# USBPiano.net
KiCad netlist of a schematic drawn in EAGLE
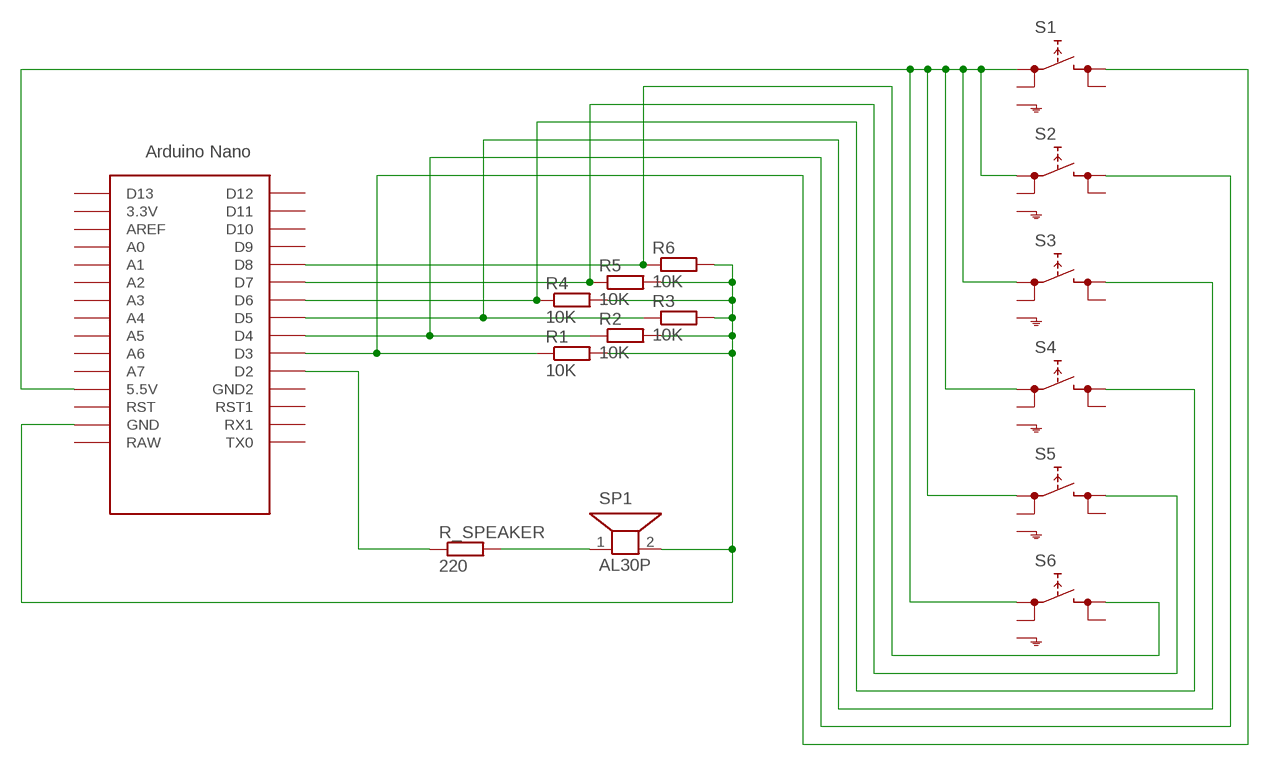
[diagram p0: schematic, sheet 1]

(export (version "E")
  (design (tool "Eeschema 10.0.6"))
  (components
    (comp (ref "R1")
      (value "10K")
      (footprint "eagle-import:M0805")
      (libsource (lib "eagle-import") (part "R-EU_M0805"))
    )
    (comp (ref "R2")
      (value "10K")
      (footprint "eagle-import:M0805")
      (libsource (lib "eagle-import") (part "R-EU_M0805"))
    )
    (comp (ref "R3")
      (value "10K")
      (footprint "eagle-import:M0805")
      (libsource (lib "eagle-import") (part "R-EU_M0805"))
    )
    (comp (ref "R4")
      (value "10K")
      (footprint "eagle-import:M0805")
      (libsource (lib "eagle-import") (part "R-EU_M0805"))
    )
    (comp (ref "R5")
      (value "10K")
      (footprint "eagle-import:M0805")
      (libsource (lib "eagle-import") (part "R-EU_M0805"))
    )
    (comp (ref "R6")
      (value "10K")
      (footprint "eagle-import:M0805")
      (libsource (lib "eagle-import") (part "R-EU_M0805"))
    )
    (comp (ref "R_SPEAKER")
      (value "220")
      (footprint "eagle-import:M0805")
      (libsource (lib "eagle-import") (part "R-EU_M0805"))
    )
    (comp (ref "S1")
      (value "SKHMPSE010")
      (footprint "eagle-import:SKHMPXE010")
      (libsource (lib "eagle-import") (part "SKHMPE010S"))
    )
    (comp (ref "S2")
      (value "SKHMPSE010")
      (footprint "eagle-import:SKHMPXE010")
      (libsource (lib "eagle-import") (part "SKHMPE010S"))
    )
    (comp (ref "S3")
      (value "SKHMPSE010")
      (footprint "eagle-import:SKHMPXE010")
      (libsource (lib "eagle-import") (part "SKHMPE010S"))
    )
    (comp (ref "S4")
      (value "SKHMPSE010")
      (footprint "eagle-import:SKHMPXE010")
      (libsource (lib "eagle-import") (part "SKHMPE010S"))
    )
    (comp (ref "S5")
      (value "SKHMPSE010")
      (footprint "eagle-import:SKHMPXE010")
      (libsource (lib "eagle-import") (part "SKHMPE010S"))
    )
    (comp (ref "S6")
      (value "SKHMPSE010")
      (footprint "eagle-import:SKHMPXE010")
      (libsource (lib "eagle-import") (part "SKHMPE010S"))
    )
    (comp (ref "SP1")
      (value "AL30P")
      (footprint "eagle-import:AL30P")
      (libsource (lib "eagle-import") (part "AL30P"))
    )
    (comp (ref "U$1")
      (value "NANO")
      (footprint "eagle-import:NANO")
      (libsource (lib "eagle-import") (part "NANO"))
    )
  )
  (nets
    (net (code "1") (name "Net-(R1-Pad2)") (class "Default")
      (node (ref "R1") (pin "2") (pinfunction "2_2") (pintype "passive"))
      (node (ref "R2") (pin "2") (pinfunction "2_2") (pintype "passive"))
      (node (ref "R3") (pin "2") (pinfunction "2_2") (pintype "passive"))
      (node (ref "R4") (pin "2") (pinfunction "2_2") (pintype "passive"))
      (node (ref "R5") (pin "2") (pinfunction "2_2") (pintype "passive"))
      (node (ref "R6") (pin "2") (pinfunction "2_2") (pintype "passive"))
      (node (ref "SP1") (pin "2") (pinfunction "2_2") (pintype "passive"))
      (node (ref "U$1") (pin "GND") (pinfunction "GND_GND") (pintype "bidirectional"))
    )
    (net (code "2") (name "Net-(R_SPEAKER-Pad1)") (class "Default")
      (node (ref "R_SPEAKER") (pin "1") (pinfunction "1_1") (pintype "passive"))
      (node (ref "U$1") (pin "D2") (pinfunction "D2_D2") (pintype "bidirectional"))
    )
    (net (code "3") (name "Net-(R_SPEAKER-Pad2)") (class "Default")
      (node (ref "R_SPEAKER") (pin "2") (pinfunction "2_2") (pintype "passive"))
      (node (ref "SP1") (pin "1") (pinfunction "1_1") (pintype "passive"))
    )
    (net (code "4") (name "Net-(S1-1.1)") (class "Default")
      (node (ref "S1") (pin "1") (pinfunction "1.1_1") (pintype "passive"))
      (node (ref "S2") (pin "1") (pinfunction "1.1_1") (pintype "passive"))
      (node (ref "S3") (pin "1") (pinfunction "1.1_1") (pintype "passive"))
      (node (ref "S4") (pin "1") (pinfunction "1.1_1") (pintype "passive"))
      (node (ref "S5") (pin "1") (pinfunction "1.1_1") (pintype "passive"))
      (node (ref "S6") (pin "1") (pinfunction "1.1_1") (pintype "passive"))
      (node (ref "U$1") (pin "5V") (pinfunction "5.5V_5V") (pintype "bidirectional"))
    )
    (net (code "5") (name "Net-(S1-2.1)") (class "Default")
      (node (ref "R1") (pin "1") (pinfunction "1_1") (pintype "passive"))
      (node (ref "S1") (pin "3") (pinfunction "2.1_3") (pintype "passive"))
      (node (ref "U$1") (pin "D3") (pinfunction "D3_D3") (pintype "bidirectional"))
    )
    (net (code "6") (name "Net-(S2-2.1)") (class "Default")
      (node (ref "R2") (pin "1") (pinfunction "1_1") (pintype "passive"))
      (node (ref "S2") (pin "3") (pinfunction "2.1_3") (pintype "passive"))
      (node (ref "U$1") (pin "D4") (pinfunction "D4_D4") (pintype "bidirectional"))
    )
    (net (code "7") (name "Net-(S3-2.1)") (class "Default")
      (node (ref "R3") (pin "1") (pinfunction "1_1") (pintype "passive"))
      (node (ref "S3") (pin "3") (pinfunction "2.1_3") (pintype "passive"))
      (node (ref "U$1") (pin "D5") (pinfunction "D5_D5") (pintype "bidirectional"))
    )
    (net (code "8") (name "Net-(S4-2.1)") (class "Default")
      (node (ref "R4") (pin "1") (pinfunction "1_1") (pintype "passive"))
      (node (ref "S4") (pin "3") (pinfunction "2.1_3") (pintype "passive"))
      (node (ref "U$1") (pin "D6") (pinfunction "D6_D6") (pintype "bidirectional"))
    )
    (net (code "9") (name "Net-(S5-2.1)") (class "Default")
      (node (ref "R5") (pin "1") (pinfunction "1_1") (pintype "passive"))
      (node (ref "S5") (pin "3") (pinfunction "2.1_3") (pintype "passive"))
      (node (ref "U$1") (pin "D7") (pinfunction "D7_D7") (pintype "bidirectional"))
    )
    (net (code "10") (name "Net-(S6-2.1)") (class "Default")
      (node (ref "R6") (pin "1") (pinfunction "1_1") (pintype "passive"))
      (node (ref "S6") (pin "3") (pinfunction "2.1_3") (pintype "passive"))
      (node (ref "U$1") (pin "D8") (pinfunction "D8_D8") (pintype "bidirectional"))
    )
    (net (code "11") (name "unconnected-(S1-1.2-Pad2)") (class "Default")
      (node (ref "S1") (pin "2") (pinfunction "1.2_2") (pintype "passive"))
    )
    (net (code "12") (name "unconnected-(S1-2.2-Pad4)") (class "Default")
      (node (ref "S1") (pin "4") (pinfunction "2.2_4") (pintype "passive"))
    )
    (net (code "13") (name "unconnected-(S1-SH-Pad5)") (class "Default")
      (node (ref "S1") (pin "5") (pinfunction "SH_5") (pintype "passive"))
    )
    (net (code "14") (name "unconnected-(S2-1.2-Pad2)") (class "Default")
      (node (ref "S2") (pin "2") (pinfunction "1.2_2") (pintype "passive"))
    )
    (net (code "15") (name "unconnected-(S2-2.2-Pad4)") (class "Default")
      (node (ref "S2") (pin "4") (pinfunction "2.2_4") (pintype "passive"))
    )
    (net (code "16") (name "unconnected-(S2-SH-Pad5)") (class "Default")
      (node (ref "S2") (pin "5") (pinfunction "SH_5") (pintype "passive"))
    )
    (net (code "17") (name "unconnected-(S3-1.2-Pad2)") (class "Default")
      (node (ref "S3") (pin "2") (pinfunction "1.2_2") (pintype "passive"))
    )
    (net (code "18") (name "unconnected-(S3-2.2-Pad4)") (class "Default")
      (node (ref "S3") (pin "4") (pinfunction "2.2_4") (pintype "passive"))
    )
    (net (code "19") (name "unconnected-(S3-SH-Pad5)") (class "Default")
      (node (ref "S3") (pin "5") (pinfunction "SH_5") (pintype "passive"))
    )
    (net (code "20") (name "unconnected-(S4-1.2-Pad2)") (class "Default")
      (node (ref "S4") (pin "2") (pinfunction "1.2_2") (pintype "passive"))
    )
    (net (code "21") (name "unconnected-(S4-2.2-Pad4)") (class "Default")
      (node (ref "S4") (pin "4") (pinfunction "2.2_4") (pintype "passive"))
    )
    (net (code "22") (name "unconnected-(S4-SH-Pad5)") (class "Default")
      (node (ref "S4") (pin "5") (pinfunction "SH_5") (pintype "passive"))
    )
    (net (code "23") (name "unconnected-(S5-1.2-Pad2)") (class "Default")
      (node (ref "S5") (pin "2") (pinfunction "1.2_2") (pintype "passive"))
    )
    (net (code "24") (name "unconnected-(S5-2.2-Pad4)") (class "Default")
      (node (ref "S5") (pin "4") (pinfunction "2.2_4") (pintype "passive"))
    )
    (net (code "25") (name "unconnected-(S5-SH-Pad5)") (class "Default")
      (node (ref "S5") (pin "5") (pinfunction "SH_5") (pintype "passive"))
    )
    (net (code "26") (name "unconnected-(S6-1.2-Pad2)") (class "Default")
      (node (ref "S6") (pin "2") (pinfunction "1.2_2") (pintype "passive"))
    )
    (net (code "27") (name "unconnected-(S6-2.2-Pad4)") (class "Default")
      (node (ref "S6") (pin "4") (pinfunction "2.2_4") (pintype "passive"))
    )
    (net (code "28") (name "unconnected-(S6-SH-Pad5)") (class "Default")
      (node (ref "S6") (pin "5") (pinfunction "SH_5") (pintype "passive"))
    )
    (net (code "29") (name "unconnected-(U$1-GND2-PadGND1)") (class "Default")
      (node (ref "U$1") (pin "GND1") (pinfunction "GND2_GND1") (pintype "bidirectional"))
    )
    (net (code "30") (name "unconnected-(U$1-Pad3.3V)") (class "Default")
      (node (ref "U$1") (pin "3.3V") (pinfunction "3.3V_3.3V") (pintype "bidirectional"))
    )
    (net (code "31") (name "unconnected-(U$1-PadA0)") (class "Default")
      (node (ref "U$1") (pin "A0") (pinfunction "A0_A0") (pintype "bidirectional"))
    )
    (net (code "32") (name "unconnected-(U$1-PadA1)") (class "Default")
      (node (ref "U$1") (pin "A1") (pinfunction "A1_A1") (pintype "bidirectional"))
    )
    (net (code "33") (name "unconnected-(U$1-PadA2)") (class "Default")
      (node (ref "U$1") (pin "A2") (pinfunction "A2_A2") (pintype "bidirectional"))
    )
    (net (code "34") (name "unconnected-(U$1-PadA3)") (class "Default")
      (node (ref "U$1") (pin "A3") (pinfunction "A3_A3") (pintype "bidirectional"))
    )
    (net (code "35") (name "unconnected-(U$1-PadA4)") (class "Default")
      (node (ref "U$1") (pin "A4") (pinfunction "A4_A4") (pintype "bidirectional"))
    )
    (net (code "36") (name "unconnected-(U$1-PadA5)") (class "Default")
      (node (ref "U$1") (pin "A5") (pinfunction "A5_A5") (pintype "bidirectional"))
    )
    (net (code "37") (name "unconnected-(U$1-PadA6)") (class "Default")
      (node (ref "U$1") (pin "A6") (pinfunction "A6_A6") (pintype "bidirectional"))
    )
    (net (code "38") (name "unconnected-(U$1-PadA7)") (class "Default")
      (node (ref "U$1") (pin "A7") (pinfunction "A7_A7") (pintype "bidirectional"))
    )
    (net (code "39") (name "unconnected-(U$1-PadAREF)") (class "Default")
      (node (ref "U$1") (pin "AREF") (pinfunction "AREF_AREF") (pintype "bidirectional"))
    )
    (net (code "40") (name "unconnected-(U$1-PadD9)") (class "Default")
      (node (ref "U$1") (pin "D9") (pinfunction "D9_D9") (pintype "bidirectional"))
    )
    (net (code "41") (name "unconnected-(U$1-PadD10)") (class "Default")
      (node (ref "U$1") (pin "D10") (pinfunction "D10_D10") (pintype "bidirectional"))
    )
    (net (code "42") (name "unconnected-(U$1-PadD11)") (class "Default")
      (node (ref "U$1") (pin "D11") (pinfunction "D11_D11") (pintype "bidirectional"))
    )
    (net (code "43") (name "unconnected-(U$1-PadD12)") (class "Default")
      (node (ref "U$1") (pin "D12") (pinfunction "D12_D12") (pintype "bidirectional"))
    )
    (net (code "44") (name "unconnected-(U$1-PadD13)") (class "Default")
      (node (ref "U$1") (pin "D13") (pinfunction "D13_D13") (pintype "bidirectional"))
    )
    (net (code "45") (name "unconnected-(U$1-PadICSP1)") (class "Default")
      (node (ref "U$1") (pin "ICSP1") (pinfunction "ICSP1_ICSP1") (pintype "bidirectional"))
    )
    (net (code "46") (name "unconnected-(U$1-PadICSP2)") (class "Default")
      (node (ref "U$1") (pin "ICSP2") (pinfunction "ICSP2_ICSP2") (pintype "bidirectional"))
    )
    (net (code "47") (name "unconnected-(U$1-PadICSP3)") (class "Default")
      (node (ref "U$1") (pin "ICSP3") (pinfunction "ICSP3_ICSP3") (pintype "bidirectional"))
    )
    (net (code "48") (name "unconnected-(U$1-PadICSP4)") (class "Default")
      (node (ref "U$1") (pin "ICSP4") (pinfunction "ICSP4_ICSP4") (pintype "bidirectional"))
    )
    (net (code "49") (name "unconnected-(U$1-PadICSP5)") (class "Default")
      (node (ref "U$1") (pin "ICSP5") (pinfunction "ICSP5_ICSP5") (pintype "bidirectional"))
    )
    (net (code "50") (name "unconnected-(U$1-PadICSP6)") (class "Default")
      (node (ref "U$1") (pin "ICSP6") (pinfunction "ICSP6_ICSP6") (pintype "bidirectional"))
    )
    (net (code "51") (name "unconnected-(U$1-PadRAW)") (class "Default")
      (node (ref "U$1") (pin "RAW") (pinfunction "RAW_RAW") (pintype "bidirectional"))
    )
    (net (code "52") (name "unconnected-(U$1-PadRST)") (class "Default")
      (node (ref "U$1") (pin "RST") (pinfunction "RST_RST") (pintype "bidirectional"))
    )
    (net (code "53") (name "unconnected-(U$1-PadRST1)") (class "Default")
      (node (ref "U$1") (pin "RST1") (pinfunction "RST1_RST1") (pintype "bidirectional"))
    )
    (net (code "54") (name "unconnected-(U$1-PadRX1)") (class "Default")
      (node (ref "U$1") (pin "RX1") (pinfunction "RX1_RX1") (pintype "bidirectional"))
    )
    (net (code "55") (name "unconnected-(U$1-PadTX0)") (class "Default")
      (node (ref "U$1") (pin "TX0") (pinfunction "TX0_TX0") (pintype "bidirectional"))
    )
  )
)
